# Copy_of_MCU_and_CLK.net
KiCad netlist of a schematic drawn in Altium Designer
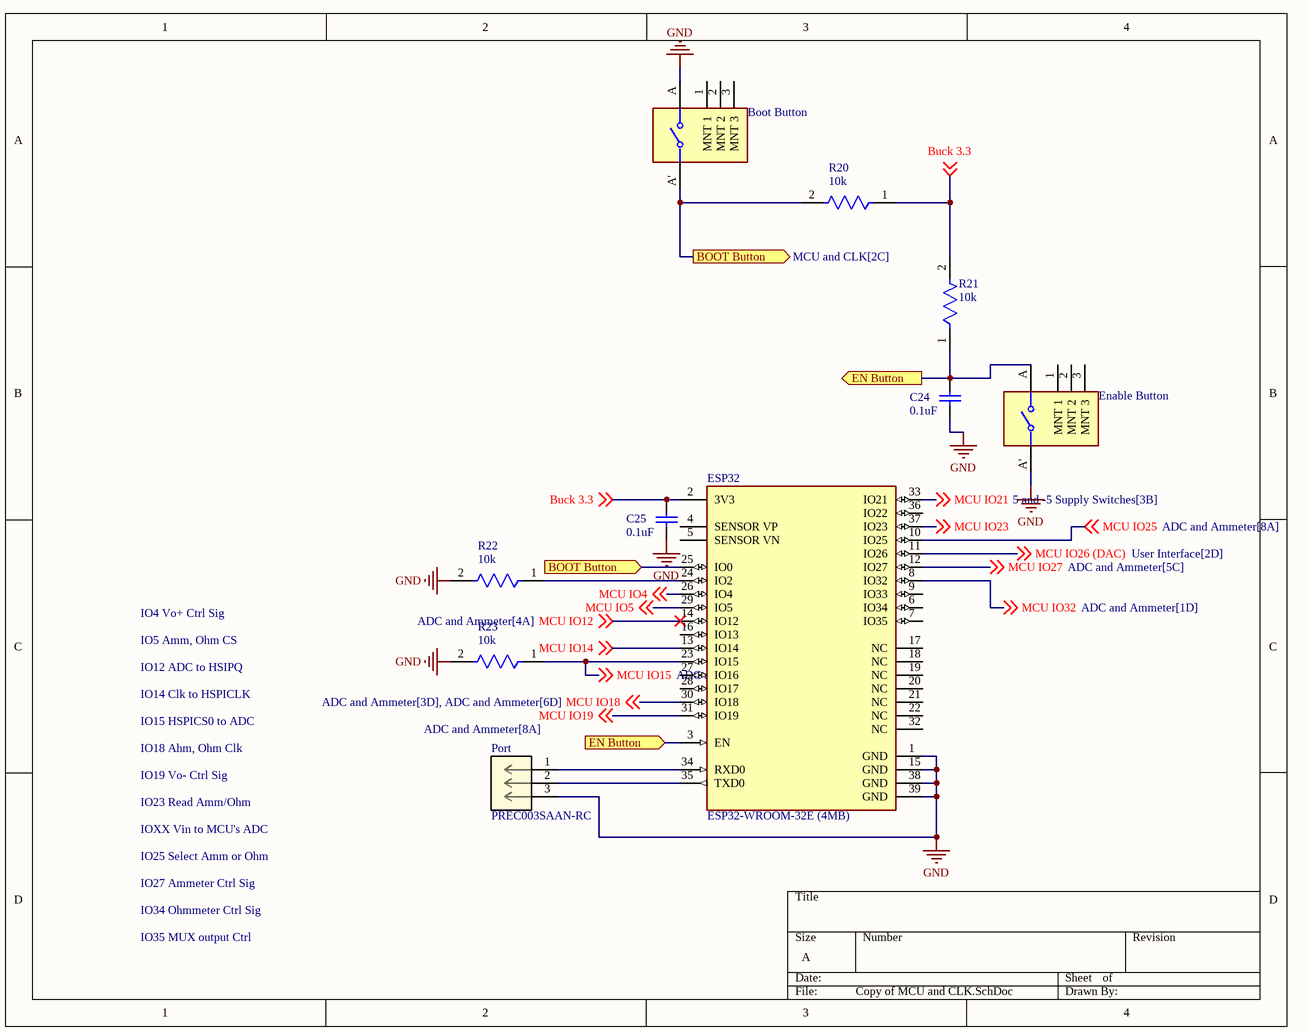
[diagram p0: Copy of MCU and CLK.SchDoc]

(export (version "E")
  (design (tool "Eeschema 10.0.6"))
  (components
    (comp (ref "Boot Button")
      (value "EVP-AKE31A")
      (footprint "FP-EVP-AKE31A-MFG")
      (description "3.8MM X 1.9MM / 1.6N / 0.12MM ST")
      (fields
        (field (name "OCTOPART") "https://octopart.com/evp-ake31a-panasonic-84742583")
        (field (name "MANUFACTURER") "Panasonic")
      )
      (libsource (lib "Altium Content Vault") (part "c4ff99993c460dbb96384a32340d491"))
    )
    (comp (ref "C24")
      (value "0.1uF")
      (footprint "CAPC2013X94X50LL20T25")
      (fields
        (field (name "PART NUMBER") "08055C104JAT4A")
        (field (name "MANUFACTURER") "AVX Interconnect / Elco")
      )
      (libsource (lib "Altium Content Vault") (part "CAP"))
    )
    (comp (ref "C25")
      (value "0.1uF")
      (footprint "CAPC2013X94X50LL20T25")
      (fields
        (field (name "PART NUMBER") "08055C104JAT4A")
        (field (name "MANUFACTURER") "AVX Interconnect / Elco")
      )
      (libsource (lib "Altium Content Vault") (part "CAP"))
    )
    (comp (ref "Enable Button")
      (value "EVP-AKE31A")
      (footprint "FP-EVP-AKE31A-MFG")
      (description "3.8MM X 1.9MM / 1.6N / 0.12MM ST")
      (fields
        (field (name "OCTOPART") "https://octopart.com/evp-ake31a-panasonic-84742583")
        (field (name "MANUFACTURER") "Panasonic")
      )
      (libsource (lib "Altium Content Vault") (part "c4ff99993c460dbb96384a32340d491"))
    )
    (comp (ref "ESP32")
      (value "ESP32-WROOM-32E (4MB)")
      (footprint "FP-ESP32-WROOM-32E_4MB-MFG")
      (description "RX TXRX MOD WIFI TRACE ANT SMD")
      (libsource (lib "Altium Content Vault") (part "7f842c3463a9561e2f6f9fdcd687e0f"))
    )
    (comp (ref "Port")
      (value "PREC003SAAN-RC")
      (footprint "PREC003SAAN-RC:CONN_PREC003SAAN-RC_SUL")
      (description "No Description Available")
      (libsource (lib "PREC003SAAN-RC") (part "PREC003SAAN-RC"))
    )
    (comp (ref "R20")
      (value "10k")
      (footprint "FP-RK73H1J-IPC_B")
      (description "10kΩ ±1% 0.1W Chip Resistor 0603 Thick Film AEC-Q200 Qualified")
      (fields (field (name "TOLERANCE") "1%"))
      (libsource (lib "Altium Content Vault") (part "1029c3af85768c4190bb7ad29bc67b5"))
    )
    (comp (ref "R21")
      (value "10k")
      (footprint "FP-RK73H1J-IPC_B")
      (description "10kΩ ±1% 0.1W Chip Resistor 0603 Thick Film AEC-Q200 Qualified")
      (fields (field (name "TOLERANCE") "1%"))
      (libsource (lib "Altium Content Vault") (part "1029c3af85768c4190bb7ad29bc67b5"))
    )
    (comp (ref "R22")
      (value "10k")
      (footprint "FP-RK73H1J-IPC_B")
      (description "10kΩ ±1% 0.1W Chip Resistor 0603 Thick Film AEC-Q200 Qualified")
      (fields (field (name "TOLERANCE") "1%"))
      (libsource (lib "Altium Content Vault") (part "1029c3af85768c4190bb7ad29bc67b5"))
    )
    (comp (ref "R23")
      (value "10k")
      (footprint "FP-RK73H1J-IPC_B")
      (description "10kΩ ±1% 0.1W Chip Resistor 0603 Thick Film AEC-Q200 Qualified")
      (fields (field (name "TOLERANCE") "1%"))
      (libsource (lib "Altium Content Vault") (part "1029c3af85768c4190bb7ad29bc67b5"))
    )
  )
  (nets
    (net (code "1") (name "/BOOT Button") (class "Default")
      (node (ref "Boot Button") (pin "A'") (pinfunction "A'_A'") (pintype "passive"))
      (node (ref "ESP32") (pin "25") (pinfunction "IO0_25") (pintype "bidirectional"))
      (node (ref "R20") (pin "2") (pinfunction "2_2") (pintype "passive"))
    )
    (net (code "2") (name "/EN Button") (class "Default")
      (node (ref "C24") (pin "2") (pinfunction "2_2") (pintype "passive"))
      (node (ref "ESP32") (pin "3") (pinfunction "EN_3") (pintype "input"))
      (node (ref "Enable Button") (pin "A") (pinfunction "A_A") (pintype "passive"))
      (node (ref "R21") (pin "1") (pinfunction "1_1") (pintype "passive"))
    )
    (net (code "3") (name "Buck 3.3") (class "Default")
      (node (ref "C25") (pin "2") (pinfunction "2_2") (pintype "passive"))
      (node (ref "ESP32") (pin "2") (pinfunction "3V3_2") (pintype "power_in"))
      (node (ref "R20") (pin "1") (pinfunction "1_1") (pintype "passive"))
      (node (ref "R21") (pin "2") (pinfunction "2_2") (pintype "passive"))
    )
    (net (code "4") (name "GND") (class "Default")
      (node (ref "Boot Button") (pin "A") (pinfunction "A_A") (pintype "passive"))
      (node (ref "C24") (pin "1") (pinfunction "1_1") (pintype "passive"))
      (node (ref "C25") (pin "1") (pinfunction "1_1") (pintype "passive"))
      (node (ref "ESP32") (pin "1") (pinfunction "GND_1") (pintype "power_in"))
      (node (ref "ESP32") (pin "15") (pinfunction "GND_15") (pintype "power_in"))
      (node (ref "ESP32") (pin "38") (pinfunction "GND_38") (pintype "power_in"))
      (node (ref "ESP32") (pin "39") (pinfunction "GND_39") (pintype "power_in"))
      (node (ref "Enable Button") (pin "A'") (pinfunction "A'_A'") (pintype "passive"))
      (node (ref "Port") (pin "3") (pinfunction "3_3") (pintype "passive"))
      (node (ref "R22") (pin "2") (pinfunction "2_2") (pintype "passive"))
      (node (ref "R23") (pin "2") (pinfunction "2_2") (pintype "passive"))
    )
    (net (code "5") (name "MCU IO4") (class "Default")
      (node (ref "ESP32") (pin "26") (pinfunction "IO4_26") (pintype "bidirectional"))
    )
    (net (code "6") (name "MCU IO5") (class "Default")
      (node (ref "ESP32") (pin "29") (pinfunction "IO5_29") (pintype "bidirectional"))
    )
    (net (code "7") (name "MCU IO12") (class "Default")
      (node (ref "ESP32") (pin "14") (pinfunction "IO12_14") (pintype "bidirectional"))
    )
    (net (code "8") (name "MCU IO14") (class "Default")
      (node (ref "ESP32") (pin "13") (pinfunction "IO14_13") (pintype "bidirectional"))
    )
    (net (code "9") (name "MCU IO15") (class "Default")
      (node (ref "ESP32") (pin "23") (pinfunction "IO15_23") (pintype "bidirectional"))
      (node (ref "R23") (pin "1") (pinfunction "1_1") (pintype "passive"))
    )
    (net (code "10") (name "MCU IO18") (class "Default")
      (node (ref "ESP32") (pin "30") (pinfunction "IO18_30") (pintype "bidirectional"))
    )
    (net (code "11") (name "MCU IO19") (class "Default")
      (node (ref "ESP32") (pin "31") (pinfunction "IO19_31") (pintype "bidirectional"))
    )
    (net (code "12") (name "MCU IO21") (class "Default")
      (node (ref "ESP32") (pin "33") (pinfunction "IO21_33") (pintype "bidirectional"))
    )
    (net (code "13") (name "MCU IO23") (class "Default")
      (node (ref "ESP32") (pin "37") (pinfunction "IO23_37") (pintype "bidirectional"))
    )
    (net (code "14") (name "MCU IO25") (class "Default")
      (node (ref "ESP32") (pin "10") (pinfunction "IO25_10") (pintype "bidirectional"))
    )
    (net (code "15") (name "MCU IO26 (DAC)") (class "Default")
      (node (ref "ESP32") (pin "11") (pinfunction "IO26_11") (pintype "bidirectional"))
    )
    (net (code "16") (name "MCU IO27") (class "Default")
      (node (ref "ESP32") (pin "12") (pinfunction "IO27_12") (pintype "bidirectional"))
    )
    (net (code "17") (name "MCU IO32") (class "Default")
      (node (ref "ESP32") (pin "8") (pinfunction "IO32_8") (pintype "bidirectional"))
    )
    (net (code "18") (name "Net-(ESP32-IO2)") (class "Default")
      (node (ref "ESP32") (pin "24") (pinfunction "IO2_24") (pintype "bidirectional"))
      (node (ref "R22") (pin "1") (pinfunction "1_1") (pintype "passive"))
    )
    (net (code "19") (name "Net-(ESP32-RXD0)") (class "Default")
      (node (ref "ESP32") (pin "34") (pinfunction "RXD0_34") (pintype "input"))
      (node (ref "Port") (pin "1") (pinfunction "1_1") (pintype "passive"))
    )
    (net (code "20") (name "Net-(ESP32-TXD0)") (class "Default")
      (node (ref "ESP32") (pin "35") (pinfunction "TXD0_35") (pintype "output"))
      (node (ref "Port") (pin "2") (pinfunction "2_2") (pintype "passive"))
    )
    (net (code "21") (name "unconnected-(Boot Button-MNT_1-Pad1)") (class "Default")
      (node (ref "Boot Button") (pin "1") (pinfunction "MNT_1_1") (pintype "passive"))
    )
    (net (code "22") (name "unconnected-(Boot Button-MNT_2-Pad2)") (class "Default")
      (node (ref "Boot Button") (pin "2") (pinfunction "MNT_2_2") (pintype "passive"))
    )
    (net (code "23") (name "unconnected-(Boot Button-MNT_3-Pad3)") (class "Default")
      (node (ref "Boot Button") (pin "3") (pinfunction "MNT_3_3") (pintype "passive"))
    )
    (net (code "24") (name "unconnected-(ESP32-IO13-Pad16)") (class "Default")
      (node (ref "ESP32") (pin "16") (pinfunction "IO13_16") (pintype "bidirectional"))
    )
    (net (code "25") (name "unconnected-(ESP32-IO16-Pad27)") (class "Default")
      (node (ref "ESP32") (pin "27") (pinfunction "IO16_27") (pintype "bidirectional"))
    )
    (net (code "26") (name "unconnected-(ESP32-IO17-Pad28)") (class "Default")
      (node (ref "ESP32") (pin "28") (pinfunction "IO17_28") (pintype "bidirectional"))
    )
    (net (code "27") (name "unconnected-(ESP32-IO22-Pad36)") (class "Default")
      (node (ref "ESP32") (pin "36") (pinfunction "IO22_36") (pintype "bidirectional"))
    )
    (net (code "28") (name "unconnected-(ESP32-IO33-Pad9)") (class "Default")
      (node (ref "ESP32") (pin "9") (pinfunction "IO33_9") (pintype "bidirectional"))
    )
    (net (code "29") (name "unconnected-(ESP32-IO34-Pad6)") (class "Default")
      (node (ref "ESP32") (pin "6") (pinfunction "IO34_6") (pintype "bidirectional"))
    )
    (net (code "30") (name "unconnected-(ESP32-IO35-Pad7)") (class "Default")
      (node (ref "ESP32") (pin "7") (pinfunction "IO35_7") (pintype "bidirectional"))
    )
    (net (code "31") (name "unconnected-(ESP32-NC-Pad17)") (class "Default")
      (node (ref "ESP32") (pin "17") (pinfunction "NC_17") (pintype "passive"))
    )
    (net (code "32") (name "unconnected-(ESP32-NC-Pad18)") (class "Default")
      (node (ref "ESP32") (pin "18") (pinfunction "NC_18") (pintype "passive"))
    )
    (net (code "33") (name "unconnected-(ESP32-NC-Pad19)") (class "Default")
      (node (ref "ESP32") (pin "19") (pinfunction "NC_19") (pintype "passive"))
    )
    (net (code "34") (name "unconnected-(ESP32-NC-Pad20)") (class "Default")
      (node (ref "ESP32") (pin "20") (pinfunction "NC_20") (pintype "passive"))
    )
    (net (code "35") (name "unconnected-(ESP32-NC-Pad21)") (class "Default")
      (node (ref "ESP32") (pin "21") (pinfunction "NC_21") (pintype "passive"))
    )
    (net (code "36") (name "unconnected-(ESP32-NC-Pad22)") (class "Default")
      (node (ref "ESP32") (pin "22") (pinfunction "NC_22") (pintype "passive"))
    )
    (net (code "37") (name "unconnected-(ESP32-NC-Pad32)") (class "Default")
      (node (ref "ESP32") (pin "32") (pinfunction "NC_32") (pintype "passive"))
    )
    (net (code "38") (name "unconnected-(ESP32-SENSOR_VN-Pad5)") (class "Default")
      (node (ref "ESP32") (pin "5") (pinfunction "SENSOR_VN_5") (pintype "passive"))
    )
    (net (code "39") (name "unconnected-(ESP32-SENSOR_VP-Pad4)") (class "Default")
      (node (ref "ESP32") (pin "4") (pinfunction "SENSOR_VP_4") (pintype "passive"))
    )
    (net (code "40") (name "unconnected-(Enable Button-MNT_1-Pad1)") (class "Default")
      (node (ref "Enable Button") (pin "1") (pinfunction "MNT_1_1") (pintype "passive"))
    )
    (net (code "41") (name "unconnected-(Enable Button-MNT_2-Pad2)") (class "Default")
      (node (ref "Enable Button") (pin "2") (pinfunction "MNT_2_2") (pintype "passive"))
    )
    (net (code "42") (name "unconnected-(Enable Button-MNT_3-Pad3)") (class "Default")
      (node (ref "Enable Button") (pin "3") (pinfunction "MNT_3_3") (pintype "passive"))
    )
  )
)
